# atmega32u4.net
KiCad netlist of a schematic drawn in EAGLE
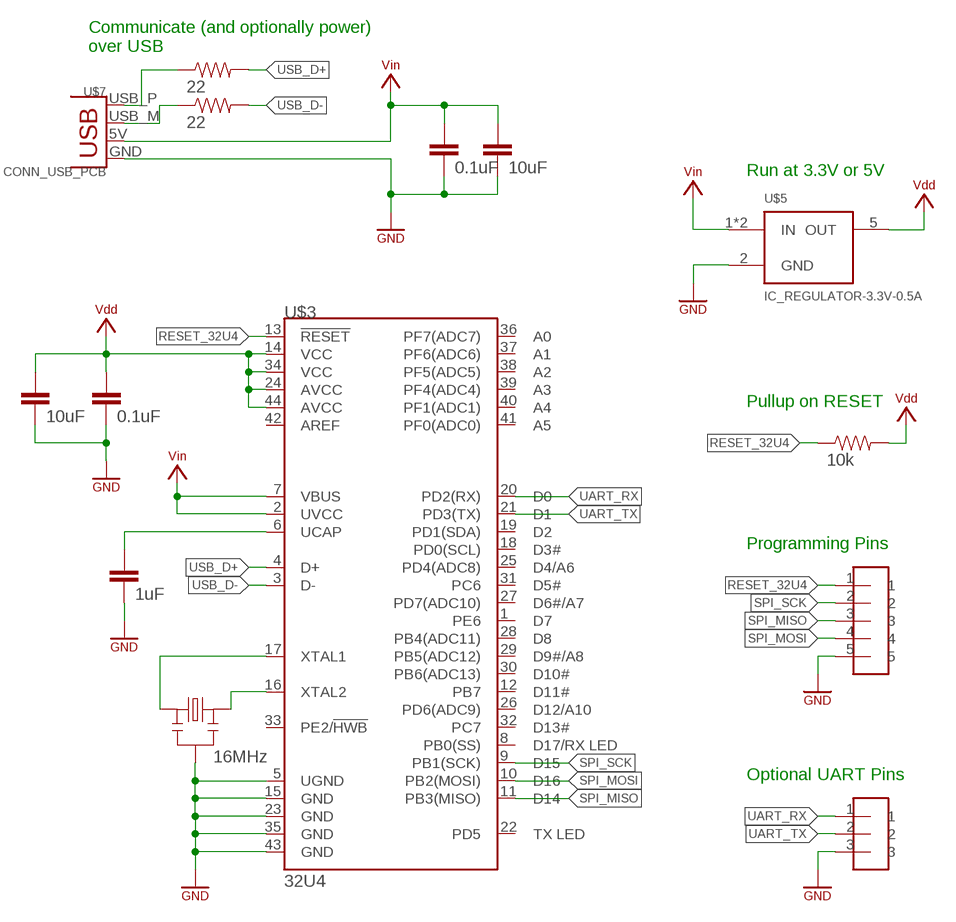
[diagram p0: schematic, sheet 1]

(export (version "E")
  (design (tool "Eeschema 10.0.6"))
  (components
    (comp (ref "C1")
      (value "0.1uF")
      (footprint "eagle-import:0805")
      (libsource (lib "eagle-import") (part "COMPONENT_CAP-0805"))
    )
    (comp (ref "C2")
      (value "10uF")
      (footprint "eagle-import:0805")
      (libsource (lib "eagle-import") (part "COMPONENT_CAP-0805"))
    )
    (comp (ref "C3")
      (value "1uF")
      (footprint "eagle-import:0805")
      (libsource (lib "eagle-import") (part "COMPONENT_CAP-0805"))
    )
    (comp (ref "C4")
      (value "0.1uF")
      (footprint "eagle-import:0805")
      (libsource (lib "eagle-import") (part "COMPONENT_CAP-0805"))
    )
    (comp (ref "C5")
      (value "10uF")
      (footprint "eagle-import:0805")
      (libsource (lib "eagle-import") (part "COMPONENT_CAP-0805"))
    )
    (comp (ref "R1")
      (value "10k")
      (footprint "eagle-import:0805")
      (libsource (lib "eagle-import") (part "COMPONENT_RESISTOR-0805"))
    )
    (comp (ref "R2")
      (value "22")
      (footprint "eagle-import:0805")
      (libsource (lib "eagle-import") (part "COMPONENT_RESISTOR-0805"))
    )
    (comp (ref "R3")
      (value "22")
      (footprint "eagle-import:0805")
      (libsource (lib "eagle-import") (part "COMPONENT_RESISTOR-0805"))
    )
    (comp (ref "U$1")
      (value "HEADER-3-TESTPOINT")
      (footprint "eagle-import:TESTPOINT-3")
      (libsource (lib "eagle-import") (part "HEADER-3-TESTPOINT"))
    )
    (comp (ref "U$2")
      (value "HEADER-5-TESTPOINT")
      (footprint "eagle-import:TESTPOINT-5")
      (libsource (lib "eagle-import") (part "HEADER-5-TESTPOINT"))
    )
    (comp (ref "U$3")
      (value "32U4")
      (footprint "eagle-import:TQFP44")
      (libsource (lib "eagle-import") (part "MICRO_ATMEGA32U4TQFP-44"))
    )
    (comp (ref "U$5")
      (value "IC_REGULATOR-3.3V-0.5A")
      (footprint "eagle-import:SOT23-5")
      (libsource (lib "eagle-import") (part "IC_REGULATOR-3.3V-0.5A"))
    )
    (comp (ref "U$7")
      (value "CONN_USB_PCB")
      (footprint "eagle-import:USB-PCB")
      (libsource (lib "eagle-import") (part "CONN_USB_PCB"))
    )
    (comp (ref "Y1")
      (value "16MHz")
      (footprint "eagle-import:RESONATOR-SMD")
      (libsource (lib "eagle-import") (part "COMPONENT_RESONATOR-1.2MM-PITCH"))
    )
  )
  (nets
    (net (code "1") (name "Net-(U$3-UCAP)") (class "Default")
      (node (ref "C3") (pin "1") (pinfunction "1_1") (pintype "passive"))
      (node (ref "U$3") (pin "6") (pinfunction "UCAP_6") (pintype "bidirectional"))
    )
    (net (code "2") (name "Net-(U$3-XTAL1)") (class "Default")
      (node (ref "U$3") (pin "17") (pinfunction "XTAL1_17") (pintype "bidirectional"))
      (node (ref "Y1") (pin "1") (pinfunction "1_1") (pintype "passive"))
    )
    (net (code "3") (name "Net-(U$3-XTAL2)") (class "Default")
      (node (ref "U$3") (pin "16") (pinfunction "XTAL2_16") (pintype "bidirectional"))
      (node (ref "Y1") (pin "3") (pinfunction "3_3") (pintype "passive"))
    )
    (net (code "4") (name "Net-(U$7-D+)") (class "Default")
      (node (ref "R2") (pin "1") (pinfunction "1_1") (pintype "passive"))
      (node (ref "U$7") (pin "USB_P") (pinfunction "D+_USB_P") (pintype "bidirectional"))
    )
    (net (code "5") (name "Net-(U$7-D-)") (class "Default")
      (node (ref "R3") (pin "1") (pinfunction "1_1") (pintype "passive"))
      (node (ref "U$7") (pin "USB_M") (pinfunction "D-_USB_M") (pintype "bidirectional"))
    )
    (net (code "6") (name "RESET_32U4") (class "Default")
      (node (ref "R1") (pin "1") (pinfunction "1_1") (pintype "passive"))
      (node (ref "U$2") (pin "1") (pinfunction "1_1") (pintype "bidirectional"))
      (node (ref "U$3") (pin "13") (pinfunction "~{RESET}_13") (pintype "bidirectional"))
    )
    (net (code "7") (name "SPI_MISO") (class "Default")
      (node (ref "U$2") (pin "3") (pinfunction "3_3") (pintype "bidirectional"))
      (node (ref "U$3") (pin "11") (pinfunction "PB3(MISO)_11") (pintype "bidirectional"))
    )
    (net (code "8") (name "SPI_MOSI") (class "Default")
      (node (ref "U$2") (pin "4") (pinfunction "4_4") (pintype "bidirectional"))
      (node (ref "U$3") (pin "10") (pinfunction "PB2(MOSI)_10") (pintype "bidirectional"))
    )
    (net (code "9") (name "SPI_SCK") (class "Default")
      (node (ref "U$2") (pin "2") (pinfunction "2_2") (pintype "bidirectional"))
      (node (ref "U$3") (pin "9") (pinfunction "PB1(SCK)_9") (pintype "bidirectional"))
    )
    (net (code "10") (name "SYMBOL_GND") (class "Default")
      (node (ref "C1") (pin "2") (pinfunction "2_2") (pintype "passive"))
      (node (ref "C2") (pin "2") (pinfunction "2_2") (pintype "passive"))
      (node (ref "C3") (pin "2") (pinfunction "2_2") (pintype "passive"))
      (node (ref "C4") (pin "2") (pinfunction "2_2") (pintype "passive"))
      (node (ref "C5") (pin "2") (pinfunction "2_2") (pintype "passive"))
      (node (ref "U$1") (pin "3") (pinfunction "3_3") (pintype "bidirectional"))
      (node (ref "U$2") (pin "5") (pinfunction "5_5") (pintype "bidirectional"))
      (node (ref "U$3") (pin "15") (pinfunction "GND_15") (pintype "bidirectional"))
      (node (ref "U$3") (pin "23") (pinfunction "GND_23") (pintype "bidirectional"))
      (node (ref "U$3") (pin "35") (pinfunction "GND_35") (pintype "bidirectional"))
      (node (ref "U$3") (pin "43") (pinfunction "GND_43") (pintype "bidirectional"))
      (node (ref "U$3") (pin "5") (pinfunction "UGND_5") (pintype "bidirectional"))
      (node (ref "U$5") (pin "2") (pinfunction "GND_2") (pintype "bidirectional"))
      (node (ref "U$7") (pin "GND") (pinfunction "GND_GND") (pintype "bidirectional"))
      (node (ref "Y1") (pin "2") (pinfunction "2_2") (pintype "passive"))
    )
    (net (code "11") (name "SYMBOL_VDD") (class "Default")
      (node (ref "C1") (pin "1") (pinfunction "1_1") (pintype "passive"))
      (node (ref "C2") (pin "1") (pinfunction "1_1") (pintype "passive"))
      (node (ref "R1") (pin "2") (pinfunction "2_2") (pintype "passive"))
      (node (ref "U$3") (pin "14") (pinfunction "VCC_14") (pintype "bidirectional"))
      (node (ref "U$3") (pin "24") (pinfunction "AVCC_24") (pintype "bidirectional"))
      (node (ref "U$3") (pin "34") (pinfunction "VCC_34") (pintype "bidirectional"))
      (node (ref "U$3") (pin "44") (pinfunction "AVCC_44") (pintype "bidirectional"))
      (node (ref "U$5") (pin "5") (pinfunction "OUT_5") (pintype "bidirectional"))
    )
    (net (code "12") (name "SYMBOL_VIN") (class "Default")
      (node (ref "C4") (pin "1") (pinfunction "1_1") (pintype "passive"))
      (node (ref "C5") (pin "1") (pinfunction "1_1") (pintype "passive"))
      (node (ref "U$3") (pin "2") (pinfunction "UVCC_2") (pintype "bidirectional"))
      (node (ref "U$3") (pin "7") (pinfunction "VBUS_7") (pintype "bidirectional"))
      (node (ref "U$5") (pin "1") (pinfunction "IN_1") (pintype "bidirectional"))
      (node (ref "U$5") (pin "3") (pinfunction "IN_3") (pintype "bidirectional"))
      (node (ref "U$7") (pin "5V") (pinfunction "VBUS_5V") (pintype "bidirectional"))
    )
    (net (code "13") (name "UART_RX") (class "Default")
      (node (ref "U$1") (pin "1") (pinfunction "1_1") (pintype "bidirectional"))
      (node (ref "U$3") (pin "20") (pinfunction "PD2(RX)_20") (pintype "bidirectional"))
    )
    (net (code "14") (name "UART_TX") (class "Default")
      (node (ref "U$1") (pin "2") (pinfunction "2_2") (pintype "bidirectional"))
      (node (ref "U$3") (pin "21") (pinfunction "PD3(TX)_21") (pintype "bidirectional"))
    )
    (net (code "15") (name "USB_D+") (class "Default")
      (node (ref "R2") (pin "2") (pinfunction "2_2") (pintype "passive"))
      (node (ref "U$3") (pin "4") (pinfunction "D+_4") (pintype "bidirectional"))
    )
    (net (code "16") (name "USB_D-") (class "Default")
      (node (ref "R3") (pin "2") (pinfunction "2_2") (pintype "passive"))
      (node (ref "U$3") (pin "3") (pinfunction "D-_3") (pintype "bidirectional"))
    )
    (net (code "17") (name "unconnected-(U$3-AREF-Pad42)") (class "Default")
      (node (ref "U$3") (pin "42") (pinfunction "AREF_42") (pintype "bidirectional"))
    )
    (net (code "18") (name "unconnected-(U$3-PB0(SS)-Pad8)") (class "Default")
      (node (ref "U$3") (pin "8") (pinfunction "PB0(SS)_8") (pintype "bidirectional"))
    )
    (net (code "19") (name "unconnected-(U$3-PB4(ADC11)-Pad28)") (class "Default")
      (node (ref "U$3") (pin "28") (pinfunction "PB4(ADC11)_28") (pintype "bidirectional"))
    )
    (net (code "20") (name "unconnected-(U$3-PB5(ADC12)-Pad29)") (class "Default")
      (node (ref "U$3") (pin "29") (pinfunction "PB5(ADC12)_29") (pintype "bidirectional"))
    )
    (net (code "21") (name "unconnected-(U$3-PB6(ADC13)-Pad30)") (class "Default")
      (node (ref "U$3") (pin "30") (pinfunction "PB6(ADC13)_30") (pintype "bidirectional"))
    )
    (net (code "22") (name "unconnected-(U$3-PB7-Pad12)") (class "Default")
      (node (ref "U$3") (pin "12") (pinfunction "PB7_12") (pintype "bidirectional"))
    )
    (net (code "23") (name "unconnected-(U$3-PC6-Pad31)") (class "Default")
      (node (ref "U$3") (pin "31") (pinfunction "PC6_31") (pintype "bidirectional"))
    )
    (net (code "24") (name "unconnected-(U$3-PC7-Pad32)") (class "Default")
      (node (ref "U$3") (pin "32") (pinfunction "PC7_32") (pintype "bidirectional"))
    )
    (net (code "25") (name "unconnected-(U$3-PD0(SCL)-Pad18)") (class "Default")
      (node (ref "U$3") (pin "18") (pinfunction "PD0(SCL)_18") (pintype "bidirectional"))
    )
    (net (code "26") (name "unconnected-(U$3-PD1(SDA)-Pad19)") (class "Default")
      (node (ref "U$3") (pin "19") (pinfunction "PD1(SDA)_19") (pintype "bidirectional"))
    )
    (net (code "27") (name "unconnected-(U$3-PD4(ADC8)-Pad25)") (class "Default")
      (node (ref "U$3") (pin "25") (pinfunction "PD4(ADC8)_25") (pintype "bidirectional"))
    )
    (net (code "28") (name "unconnected-(U$3-PD5-Pad22)") (class "Default")
      (node (ref "U$3") (pin "22") (pinfunction "PD5_22") (pintype "bidirectional"))
    )
    (net (code "29") (name "unconnected-(U$3-PD6(ADC9)-Pad26)") (class "Default")
      (node (ref "U$3") (pin "26") (pinfunction "PD6(ADC9)_26") (pintype "bidirectional"))
    )
    (net (code "30") (name "unconnected-(U$3-PD7(ADC10)-Pad27)") (class "Default")
      (node (ref "U$3") (pin "27") (pinfunction "PD7(ADC10)_27") (pintype "bidirectional"))
    )
    (net (code "31") (name "unconnected-(U$3-PE2{slash}~{HWB}-Pad33)") (class "Default")
      (node (ref "U$3") (pin "33") (pinfunction "PE2/~{HWB}_33") (pintype "bidirectional"))
    )
    (net (code "32") (name "unconnected-(U$3-PE6-Pad1)") (class "Default")
      (node (ref "U$3") (pin "1") (pinfunction "PE6_1") (pintype "bidirectional"))
    )
    (net (code "33") (name "unconnected-(U$3-PF0(ADC0)-Pad41)") (class "Default")
      (node (ref "U$3") (pin "41") (pinfunction "PF0(ADC0)_41") (pintype "bidirectional"))
    )
    (net (code "34") (name "unconnected-(U$3-PF1(ADC1)-Pad40)") (class "Default")
      (node (ref "U$3") (pin "40") (pinfunction "PF1(ADC1)_40") (pintype "bidirectional"))
    )
    (net (code "35") (name "unconnected-(U$3-PF4(ADC4)-Pad39)") (class "Default")
      (node (ref "U$3") (pin "39") (pinfunction "PF4(ADC4)_39") (pintype "bidirectional"))
    )
    (net (code "36") (name "unconnected-(U$3-PF5(ADC5)-Pad38)") (class "Default")
      (node (ref "U$3") (pin "38") (pinfunction "PF5(ADC5)_38") (pintype "bidirectional"))
    )
    (net (code "37") (name "unconnected-(U$3-PF6(ADC6)-Pad37)") (class "Default")
      (node (ref "U$3") (pin "37") (pinfunction "PF6(ADC6)_37") (pintype "bidirectional"))
    )
    (net (code "38") (name "unconnected-(U$3-PF7(ADC7)-Pad36)") (class "Default")
      (node (ref "U$3") (pin "36") (pinfunction "PF7(ADC7)_36") (pintype "bidirectional"))
    )
  )
)
